# 03-Power.net
KiCad netlist of a schematic drawn in Altium Designer
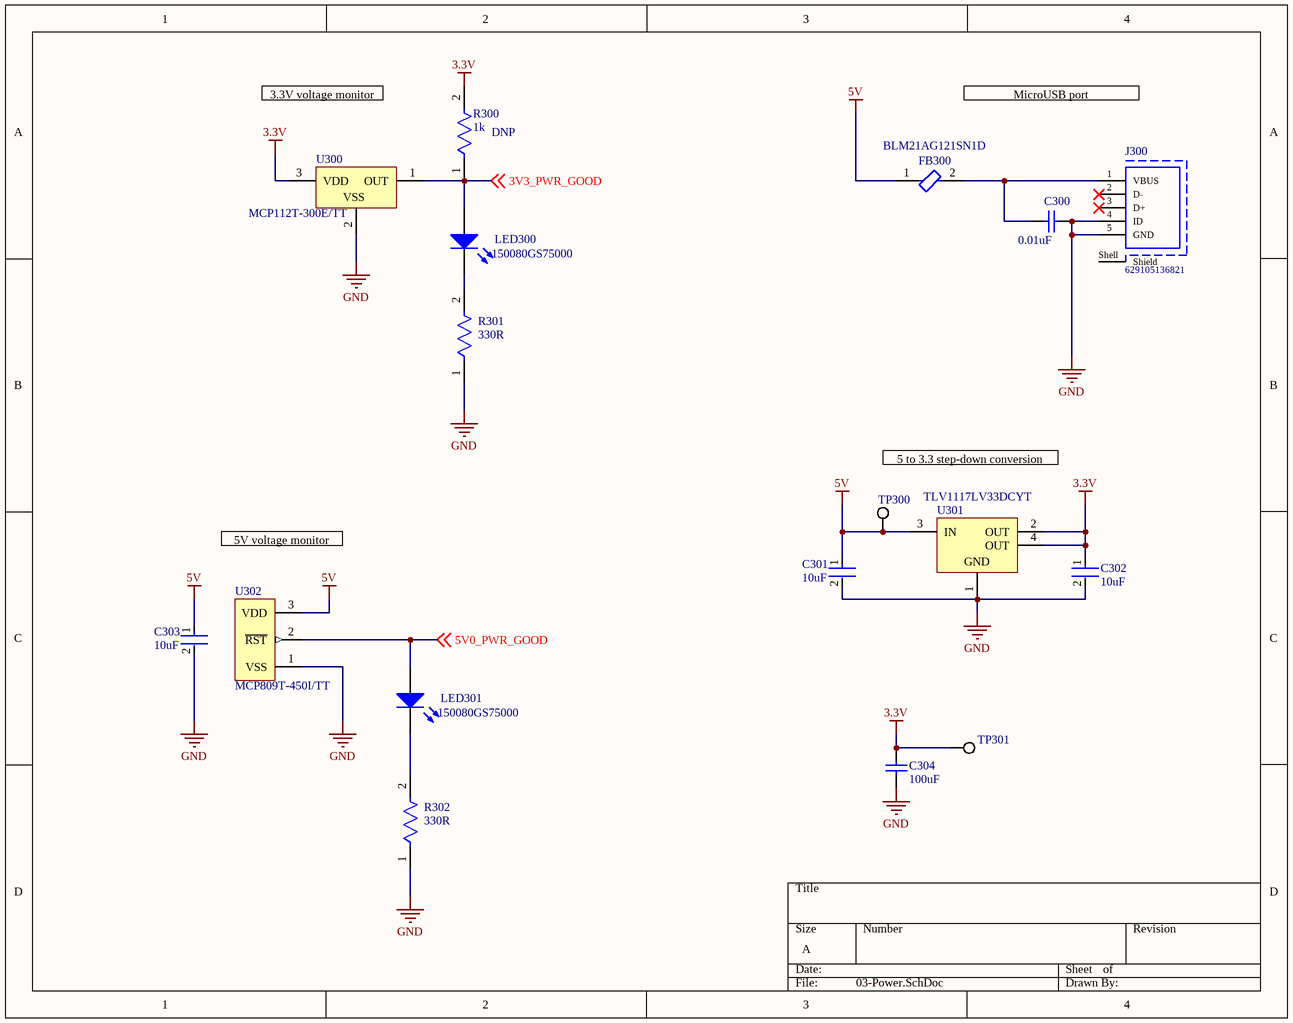
[diagram p0: 03-Power.SchDoc]

(export (version "E")
  (design (tool "Eeschema 10.0.6"))
  (components
    (comp (ref "C300")
      (value "0.01uF")
      (footprint "CAPC2013X88X50LL20T25")
      (fields
        (field (name "MANUFACTURER") "Kemet")
        (field (name "PART NUMBER") "C0805C103K5RACTU")
        (field (name "TOLERANCE") "10%")
      )
      (libsource (lib "Altium Content Vault") (part "CAP"))
    )
    (comp (ref "C301")
      (value "10uF")
      (footprint "FP-GRM21B-0_1-IPC_B")
      (description "Chip Multilayer Ceramic Capacitors for General Purpose, 0805, 10uF, X6S, 22%, 10%, 16V")
      (fields (field (name "VOLTAGE") "16V") (field (name "TOLERANCE") "10%"))
      (libsource (lib "Altium Content Vault") (part "b4654b650e69147ec39a6b967a45e02"))
    )
    (comp (ref "C302")
      (value "10uF")
      (footprint "FP-GRM21B-0_1-IPC_B")
      (description "Chip Multilayer Ceramic Capacitors for General Purpose, 0805, 10uF, X6S, 22%, 10%, 16V")
      (fields (field (name "VOLTAGE") "16V") (field (name "TOLERANCE") "10%"))
      (libsource (lib "Altium Content Vault") (part "b4654b650e69147ec39a6b967a45e02"))
    )
    (comp (ref "C303")
      (value "10uF")
      (footprint "FP-GRM21B-0_1-IPC_B")
      (description "Chip Multilayer Ceramic Capacitors for General Purpose, 0805, 10uF, X6S, 22%, 10%, 16V")
      (fields (field (name "VOLTAGE") "16V") (field (name "TOLERANCE") "10%"))
      (libsource (lib "Altium Content Vault") (part "b4654b650e69147ec39a6b967a45e02"))
    )
    (comp (ref "C304")
      (value "100uF")
      (footprint "CAPC3216X190X55ML30T25")
      (description "Chip Capacitor, 100 uF, +/- 20%, 6.3 V, -55 to 85 degC, 1206 (3216 Metric), RoHS, Tape and Reel")
      (fields (field (name "TOLERANCE") "20%") (field (name "PARTNUMBER") "GRM31CR60J107ME39L"))
      (libsource (lib "Altium Content Vault") (part "CAP-NP-2"))
    )
    (comp (ref "FB300")
      (value "BLM21AG121SN1D")
      (footprint "FP-BLM21-0_2-t0_85-e0_5-IPC_A")
      (description "FERRITE BEAD 120 OHM 0805 1LN")
      (fields (field (name "TOLERANCE") "25%"))
      (libsource (lib "Altium Content Vault") (part "5f30dd21d616792df468990f7003faa"))
    )
    (comp (ref "J300")
      (value "629105136821")
      (footprint "629105136821")
      (description "Micro USB 2.0 Type B Receptacle WR-COM, Horizontal, SMT, with Pads and Pegs")
      (fields (field (name "MANUFACTURER") "Wurth Elektronik") (field (name "PUBLISHER") "WurthElektronik"))
      (libsource (lib "Altium Content Vault") (part "WE-USB-5-1SHLD"))
    )
    (comp (ref "LED300")
      (value "150080GS75000")
      (footprint "0805_A")
      (description "SMD mono-color Chip LED, WL-SMCW, Green")
      (fields (field (name "MANUFACTURER") "Wuerth Elektronik"))
      (libsource (lib "Altium Content Vault") (part "WE-LED_K1A2-2"))
    )
    (comp (ref "LED301")
      (value "150080GS75000")
      (footprint "0805_A")
      (description "SMD mono-color Chip LED, WL-SMCW, Green")
      (fields (field (name "MANUFACTURER") "Wuerth Elektronik"))
      (libsource (lib "Altium Content Vault") (part "WE-LED_K1A2-2"))
    )
    (comp (ref "R300")
      (value "1k")
      (footprint "FP-ERA6A-IPC_C")
      (description "RES 1K OHM 0.1% 1/8W 0805")
      (fields (field (name "TOLERANCE") "0.1%"))
      (libsource (lib "Altium Content Vault") (part "1029c3af85768c4190bb7ad29bc67b5"))
    )
    (comp (ref "R301")
      (value "330R")
      (footprint "FP-ERA3A-MFG")
      (description "RES SMD 330 OHM 0.1% 1/10W 0603")
      (fields (field (name "TOLERANCE") "0.1%"))
      (libsource (lib "Altium Content Vault") (part "8db39607336c341a927600551d01821"))
    )
    (comp (ref "R302")
      (value "330R")
      (footprint "FP-ERA3A-MFG")
      (description "RES SMD 330 OHM 0.1% 1/10W 0603")
      (fields (field (name "TOLERANCE") "0.1%"))
      (libsource (lib "Altium Content Vault") (part "8db39607336c341a927600551d01821"))
    )
    (comp (ref "TP300")
      (value "5019")
      (footprint "KSTN-5019_V")
      (description "Test Point, 1 Position SMD, RoHS, Tape and Reel")
      (libsource (lib "Altium Content Vault") (part "TESTPOINT_WHITE"))
    )
    (comp (ref "TP301")
      (value "5019")
      (footprint "KSTN-5019_V")
      (description "Test Point, 1 Position SMD, RoHS, Tape and Reel")
      (libsource (lib "Altium Content Vault") (part "TESTPOINT_WHITE"))
    )
    (comp (ref "U300")
      (value "MCP112T-300E/TT")
      (footprint "SOT-23-TT3_L")
      (libsource (lib "Altium Content Vault") (part "PM-VLTD-MCP11X-SOT3"))
    )
    (comp (ref "U301")
      (value "TLV1117LV33DCYT")
      (footprint "DCY0004A_M")
      (fields (field (name "MANUFACTURER") "Texas Instruments"))
      (libsource (lib "Altium Content Vault") (part "TI-TLV1117LV33DCY4"))
    )
    (comp (ref "U302")
      (value "MCP809T-450I/TT")
      (footprint "SOT-23-TT3_N")
      (libsource (lib "Altium Content Vault") (part "PM-SCCT-MCP809-3"))
    )
  )
  (nets
    (net (code "1") (name "3.3V") (class "Default")
      (node (ref "C302") (pin "1") (pinfunction "1_1") (pintype "passive"))
      (node (ref "C304") (pin "2") (pinfunction "2_2") (pintype "passive"))
      (node (ref "R300") (pin "2") (pinfunction "2_2") (pintype "passive"))
      (node (ref "TP301") (pin "1") (pinfunction "1_1") (pintype "passive"))
      (node (ref "U300") (pin "3") (pinfunction "VDD_3") (pintype "power_in"))
      (node (ref "U301") (pin "2") (pinfunction "OUT_2") (pintype "power_in"))
      (node (ref "U301") (pin "4") (pinfunction "OUT_4") (pintype "power_in"))
    )
    (net (code "2") (name "3V3_PWR_GOOD") (class "Default")
      (node (ref "LED300") (pin "2") (pinfunction "A_2") (pintype "passive"))
      (node (ref "R300") (pin "1") (pinfunction "1_1") (pintype "passive"))
      (node (ref "U300") (pin "1") (pinfunction "OUT_1") (pintype "power_in"))
    )
    (net (code "3") (name "5V") (class "Default")
      (node (ref "C301") (pin "1") (pinfunction "1_1") (pintype "passive"))
      (node (ref "C303") (pin "1") (pinfunction "1_1") (pintype "passive"))
      (node (ref "FB300") (pin "1") (pinfunction "1_1") (pintype "passive"))
      (node (ref "TP300") (pin "1") (pinfunction "1_1") (pintype "passive"))
      (node (ref "U301") (pin "3") (pinfunction "IN_3") (pintype "power_in"))
      (node (ref "U302") (pin "3") (pinfunction "VDD_3") (pintype "power_in"))
    )
    (net (code "4") (name "5V0_PWR_GOOD") (class "Default")
      (node (ref "LED301") (pin "2") (pinfunction "A_2") (pintype "passive"))
      (node (ref "U302") (pin "2") (pinfunction "~{RST}_2") (pintype "output"))
    )
    (net (code "5") (name "GND") (class "Default")
      (node (ref "C300") (pin "2") (pinfunction "2_2") (pintype "passive"))
      (node (ref "C301") (pin "2") (pinfunction "2_2") (pintype "passive"))
      (node (ref "C302") (pin "2") (pinfunction "2_2") (pintype "passive"))
      (node (ref "C303") (pin "2") (pinfunction "2_2") (pintype "passive"))
      (node (ref "C304") (pin "1") (pinfunction "1_1") (pintype "passive"))
      (node (ref "J300") (pin "4") (pinfunction "ID_4") (pintype "passive"))
      (node (ref "J300") (pin "5") (pinfunction "GND_5") (pintype "passive"))
      (node (ref "R301") (pin "1") (pinfunction "1_1") (pintype "passive"))
      (node (ref "R302") (pin "1") (pinfunction "1_1") (pintype "passive"))
      (node (ref "U300") (pin "2") (pinfunction "VSS_2") (pintype "power_in"))
      (node (ref "U301") (pin "1") (pinfunction "GND_1") (pintype "power_in"))
      (node (ref "U302") (pin "1") (pinfunction "VSS_1") (pintype "power_in"))
    )
    (net (code "6") (name "Net-(J300-VBUS)") (class "Default")
      (node (ref "C300") (pin "1") (pinfunction "1_1") (pintype "passive"))
      (node (ref "FB300") (pin "2") (pinfunction "2_2") (pintype "passive"))
      (node (ref "J300") (pin "1") (pinfunction "VBUS_1") (pintype "passive"))
    )
    (net (code "7") (name "Net-(LED300-K)") (class "Default")
      (node (ref "LED300") (pin "1") (pinfunction "K_1") (pintype "passive"))
      (node (ref "R301") (pin "2") (pinfunction "2_2") (pintype "passive"))
    )
    (net (code "8") (name "Net-(LED301-K)") (class "Default")
      (node (ref "LED301") (pin "1") (pinfunction "K_1") (pintype "passive"))
      (node (ref "R302") (pin "2") (pinfunction "2_2") (pintype "passive"))
    )
    (net (code "9") (name "unconnected-(J300-D+-Pad3)") (class "Default")
      (node (ref "J300") (pin "3") (pinfunction "D+_3") (pintype "passive+no_connect"))
    )
    (net (code "10") (name "unconnected-(J300-D--Pad2)") (class "Default")
      (node (ref "J300") (pin "2") (pinfunction "D-_2") (pintype "passive+no_connect"))
    )
    (net (code "11") (name "unconnected-(J300-Shield-PadShell)") (class "Default")
      (node (ref "J300") (pin "Shell") (pinfunction "Shield_Shell") (pintype "passive"))
    )
  )
)
